# Sheet2.net
KiCad netlist of a schematic drawn in Altium Designer
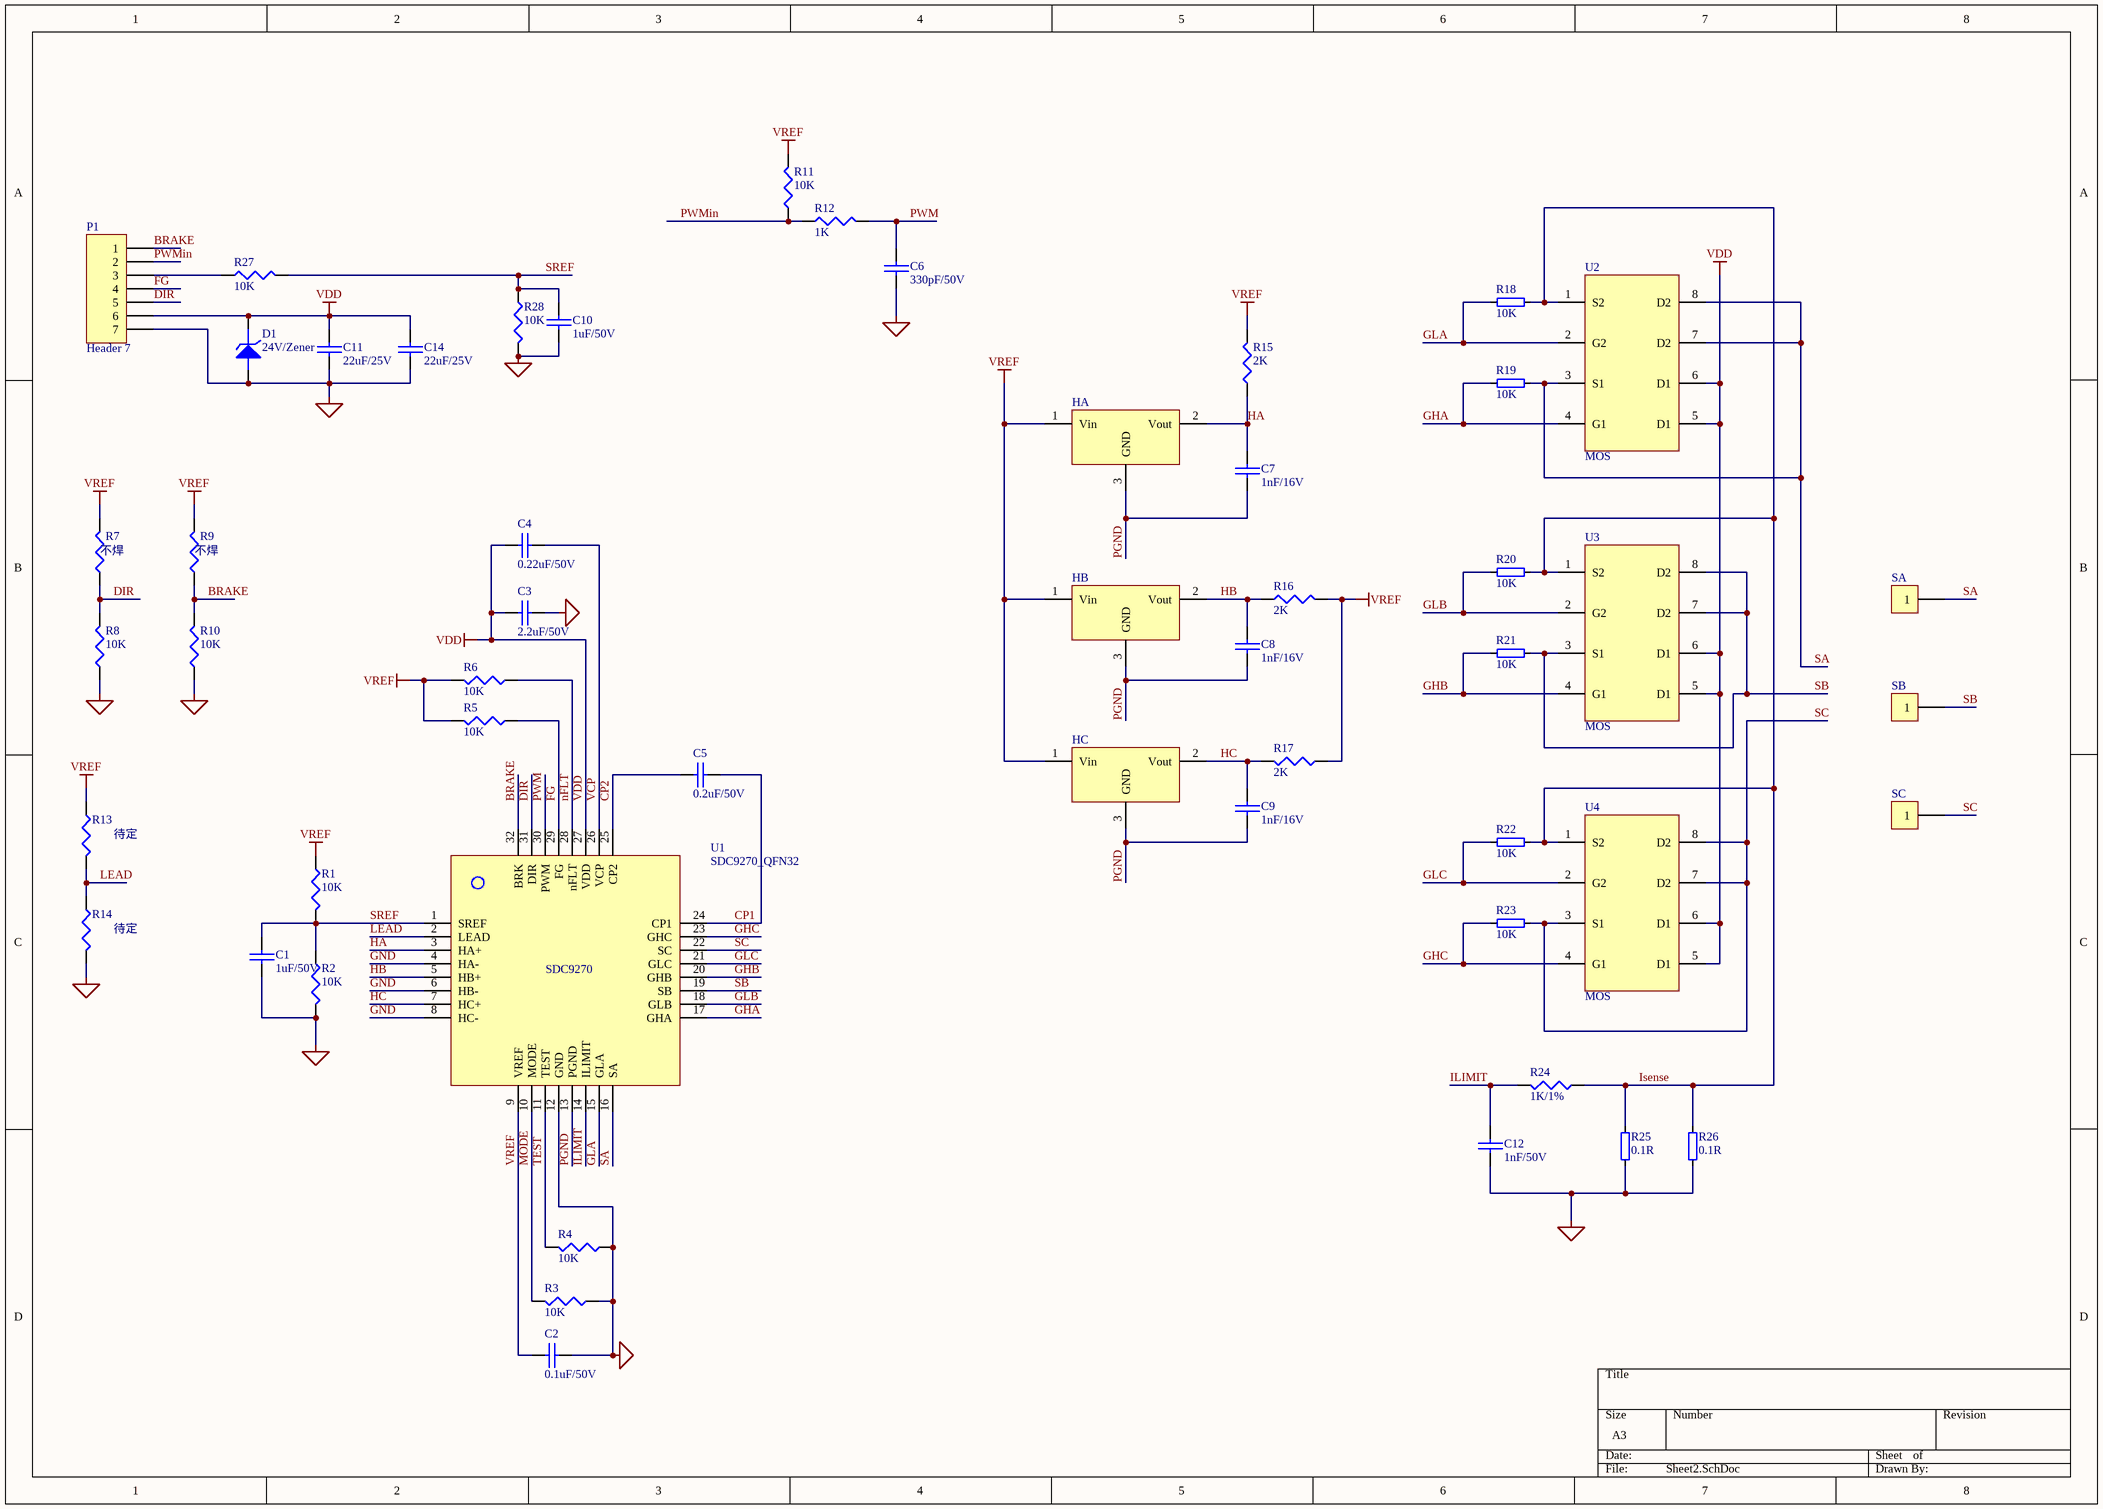
[diagram p0: Sheet2.SchDoc]

(export (version "E")
  (design (tool "Eeschema 10.0.6"))
  (components
    (comp (ref "C1")
      (value "1uF/50V")
      (footprint "6a9b1d68d1a3967c809c8143a1303d91:C0603")
      (description "C0603")
      (libsource (lib "SDC") (part "C0603"))
    )
    (comp (ref "C2")
      (value "0.1uF/50V")
      (footprint "C0603")
      (description "C0805")
      (libsource (lib "SDC") (part "C0805"))
    )
    (comp (ref "C3")
      (value "2.2uF/50V")
      (footprint "C0603")
      (description "C1206")
      (libsource (lib "SDC") (part "C1206"))
    )
    (comp (ref "C4")
      (value "0.22uF/50V")
      (footprint "C0603")
      (description "C0805")
      (libsource (lib "SDC") (part "C0805"))
    )
    (comp (ref "C5")
      (value "0.2uF/50V")
      (footprint "C0603")
      (description "C0805")
      (libsource (lib "SDC") (part "C0805"))
    )
    (comp (ref "C6")
      (value "330pF/50V")
      (footprint "C0603")
      (description "C0603")
      (libsource (lib "SDC") (part "C0603"))
    )
    (comp (ref "C7")
      (value "1nF/16V")
      (footprint "C0603")
      (description "C0603")
      (libsource (lib "SDC") (part "C0603"))
    )
    (comp (ref "C8")
      (value "1nF/16V")
      (footprint "C0603")
      (description "C0603")
      (libsource (lib "SDC") (part "C0603"))
    )
    (comp (ref "C9")
      (value "1nF/16V")
      (footprint "C0603")
      (description "C0603")
      (libsource (lib "SDC") (part "C0603"))
    )
    (comp (ref "C10")
      (value "1uF/50V")
      (footprint "C0603")
      (description "C0603")
      (libsource (lib "SDC") (part "C0603"))
    )
    (comp (ref "C11")
      (value "22uF/25V")
      (footprint "C0603")
      (description "C0603")
      (libsource (lib "SDC") (part "C0603"))
    )
    (comp (ref "C12")
      (value "1nF/50V")
      (footprint "C0603")
      (description "C0603")
      (libsource (lib "SDC") (part "C0603"))
    )
    (comp (ref "C14")
      (value "22uF/25V")
      (footprint "C0603")
      (description "C0603")
      (libsource (lib "SDC") (part "C0603"))
    )
    (comp (ref "D1")
      (value "24V/Zener")
      (footprint "SMB")
      (description "Zener Diode")
      (libsource (lib "SDC") (part "Zener_SOD-123"))
    )
    (comp (ref "HA")
      (value "HALL_SOT23-3")
      (footprint "SOT-23")
      (libsource (lib "Schlib1") (part "HALL_SOT23-3"))
    )
    (comp (ref "HB")
      (value "HALL_SOT23-3")
      (footprint "SOT-23")
      (libsource (lib "Schlib1") (part "HALL_SOT23-3"))
    )
    (comp (ref "HC")
      (value "HALL_SOT23-3")
      (footprint "SOT-23")
      (libsource (lib "Schlib1") (part "HALL_SOT23-3"))
    )
    (comp (ref "P1")
      (value "Header 7")
      (footprint "HDR1X7")
      (description "Header, 7-Pin")
      (fields (field (name "PUBLISHER") "Altium Limited"))
      (libsource (lib "Miscellaneous Connectors") (part "Header 7"))
    )
    (comp (ref "R1")
      (value "10K")
      (footprint "R0603")
      (description "R0603")
      (libsource (lib "SDC") (part "R0603"))
    )
    (comp (ref "R2")
      (value "10K")
      (footprint "R0603")
      (description "R0603")
      (libsource (lib "SDC") (part "R0603"))
    )
    (comp (ref "R3")
      (value "10K")
      (footprint "R0603")
      (description "R0603")
      (libsource (lib "SDC") (part "R0603"))
    )
    (comp (ref "R4")
      (value "10K")
      (footprint "R0603")
      (description "R0603")
      (libsource (lib "SDC") (part "R0603"))
    )
    (comp (ref "R5")
      (value "10K")
      (footprint "R0603")
      (description "R0603")
      (libsource (lib "SDC") (part "R0603"))
    )
    (comp (ref "R6")
      (value "10K")
      (footprint "R0603")
      (description "R0603")
      (libsource (lib "SDC") (part "R0603"))
    )
    (comp (ref "R7")
      (value "~")
      (footprint "R0603")
      (description "R0603")
      (libsource (lib "SDC") (part "R0603"))
    )
    (comp (ref "R8")
      (value "10K")
      (footprint "R0603")
      (description "R0603")
      (libsource (lib "SDC") (part "R0603"))
    )
    (comp (ref "R9")
      (value "~")
      (footprint "R0603")
      (description "R0603")
      (libsource (lib "SDC") (part "R0603"))
    )
    (comp (ref "R10")
      (value "10K")
      (footprint "R0603")
      (description "R0603")
      (libsource (lib "SDC") (part "R0603"))
    )
    (comp (ref "R11")
      (value "10K")
      (footprint "R0603")
      (description "R0603")
      (libsource (lib "SDC") (part "R0603"))
    )
    (comp (ref "R12")
      (value "1K")
      (footprint "R0603")
      (description "R0603")
      (libsource (lib "SDC") (part "R0603"))
    )
    (comp (ref "R13")
      (value "~")
      (footprint "R0603")
      (description "R0603")
      (libsource (lib "SDC") (part "R0603"))
    )
    (comp (ref "R14")
      (value "~")
      (footprint "R0603")
      (description "R0603")
      (libsource (lib "SDC") (part "R0603"))
    )
    (comp (ref "R15")
      (value "2K")
      (footprint "R0603")
      (description "R0603")
      (libsource (lib "SDC") (part "R0603"))
    )
    (comp (ref "R16")
      (value "2K")
      (footprint "R0603")
      (description "R0603")
      (libsource (lib "SDC") (part "R0603"))
    )
    (comp (ref "R17")
      (value "2K")
      (footprint "R0603")
      (description "R0603")
      (libsource (lib "SDC") (part "R0603"))
    )
    (comp (ref "R18") (value "10K") (footprint "R0603") (libsource (lib "SDC") (part "R1_0603")))
    (comp (ref "R19") (value "10K") (footprint "R0603") (libsource (lib "SDC") (part "R1_0603")))
    (comp (ref "R20") (value "10K") (footprint "R0603") (libsource (lib "SDC") (part "R1_0603")))
    (comp (ref "R21") (value "10K") (footprint "R0603") (libsource (lib "SDC") (part "R1_0603")))
    (comp (ref "R22") (value "10K") (footprint "R0603") (libsource (lib "SDC") (part "R1_0603")))
    (comp (ref "R23") (value "10K") (footprint "R0603") (libsource (lib "SDC") (part "R1_0603")))
    (comp (ref "R24")
      (value "1K/1%")
      (footprint "R0603")
      (description "R0603")
      (libsource (lib "SDC") (part "R0603"))
    )
    (comp (ref "R25") (value "0.1R") (footprint "R2512") (libsource (lib "SDC") (part "R2512")))
    (comp (ref "R26") (value "0.1R") (footprint "R2512") (libsource (lib "SDC") (part "R2512")))
    (comp (ref "R27")
      (value "10K")
      (footprint "R0603")
      (description "R0603")
      (libsource (lib "SDC") (part "R0603"))
    )
    (comp (ref "R28")
      (value "10K")
      (footprint "R0603")
      (description "R0603")
      (libsource (lib "SDC") (part "R0603"))
    )
    (comp (ref "SA")
      (value "~")
      (footprint "cp1")
      (description "Connector")
      (libsource (lib "Miscellaneous Devices") (part "CON1"))
    )
    (comp (ref "SB")
      (value "~")
      (footprint "cp1")
      (description "Connector")
      (libsource (lib "Miscellaneous Devices") (part "CON1"))
    )
    (comp (ref "SC")
      (value "~")
      (footprint "cp1")
      (description "Connector")
      (libsource (lib "Miscellaneous Devices") (part "CON1"))
    )
    (comp (ref "U1")
      (value "SDC9270_QFN32")
      (footprint "QFN32 (5*5)")
      (libsource (lib "9c398404867a5683d8cc0047cfd995d4") (part "SDC9270_QFN32"))
    )
    (comp (ref "U2") (value "MOS") (footprint "SOP-8") (libsource (lib "SDC") (part "MOS")))
    (comp (ref "U3") (value "MOS") (footprint "SOP-8") (libsource (lib "SDC") (part "MOS")))
    (comp (ref "U4") (value "MOS") (footprint "SOP-8") (libsource (lib "SDC") (part "MOS")))
  )
  (nets
    (net (code "1") (name "/BRAKE") (class "Default")
      (node (ref "P1") (pin "1") (pinfunction "1_1") (pintype "passive"))
      (node (ref "R10") (pin "2") (pinfunction "2_2") (pintype "passive"))
      (node (ref "R9") (pin "1") (pinfunction "1_1") (pintype "passive"))
      (node (ref "U1") (pin "32") (pinfunction "BRK_32") (pintype "passive"))
    )
    (net (code "2") (name "/CP1") (class "Default")
      (node (ref "C5") (pin "1") (pinfunction "1_1") (pintype "passive"))
      (node (ref "U1") (pin "24") (pinfunction "CP1_24") (pintype "passive"))
    )
    (net (code "3") (name "/CP2") (class "Default")
      (node (ref "C5") (pin "2") (pinfunction "2_2") (pintype "passive"))
      (node (ref "U1") (pin "25") (pinfunction "CP2_25") (pintype "passive"))
    )
    (net (code "4") (name "/DIR") (class "Default")
      (node (ref "P1") (pin "5") (pinfunction "5_5") (pintype "passive"))
      (node (ref "R7") (pin "1") (pinfunction "1_1") (pintype "passive"))
      (node (ref "R8") (pin "2") (pinfunction "2_2") (pintype "passive"))
      (node (ref "U1") (pin "31") (pinfunction "DIR_31") (pintype "passive"))
    )
    (net (code "5") (name "/FG") (class "Default")
      (node (ref "P1") (pin "4") (pinfunction "4_4") (pintype "passive"))
      (node (ref "R5") (pin "1") (pinfunction "1_1") (pintype "passive"))
      (node (ref "U1") (pin "29") (pinfunction "FG_29") (pintype "passive"))
    )
    (net (code "6") (name "/GHA") (class "Default")
      (node (ref "R19") (pin "1") (pinfunction "1_1") (pintype "passive"))
      (node (ref "U1") (pin "17") (pinfunction "GHA_17") (pintype "passive"))
      (node (ref "U2") (pin "4") (pinfunction "G1_4") (pintype "passive"))
    )
    (net (code "7") (name "/GHB") (class "Default")
      (node (ref "R21") (pin "2") (pinfunction "2_2") (pintype "passive"))
      (node (ref "U1") (pin "20") (pinfunction "GHB_20") (pintype "passive"))
      (node (ref "U3") (pin "4") (pinfunction "G1_4") (pintype "passive"))
    )
    (net (code "8") (name "/GHC") (class "Default")
      (node (ref "R23") (pin "1") (pinfunction "1_1") (pintype "passive"))
      (node (ref "U1") (pin "23") (pinfunction "GHC_23") (pintype "passive"))
      (node (ref "U4") (pin "4") (pinfunction "G1_4") (pintype "passive"))
    )
    (net (code "9") (name "/GLA") (class "Default")
      (node (ref "R18") (pin "2") (pinfunction "2_2") (pintype "passive"))
      (node (ref "U1") (pin "15") (pinfunction "GLA_15") (pintype "passive"))
      (node (ref "U2") (pin "2") (pinfunction "G2_2") (pintype "passive"))
    )
    (net (code "10") (name "/GLB") (class "Default")
      (node (ref "R20") (pin "1") (pinfunction "1_1") (pintype "passive"))
      (node (ref "U1") (pin "18") (pinfunction "GLB_18") (pintype "passive"))
      (node (ref "U3") (pin "2") (pinfunction "G2_2") (pintype "passive"))
    )
    (net (code "11") (name "/GLC") (class "Default")
      (node (ref "R22") (pin "2") (pinfunction "2_2") (pintype "passive"))
      (node (ref "U1") (pin "21") (pinfunction "GLC_21") (pintype "passive"))
      (node (ref "U4") (pin "2") (pinfunction "G2_2") (pintype "passive"))
    )
    (net (code "12") (name "/GND") (class "Default")
      (node (ref "U1") (pin "4") (pinfunction "HA-_4") (pintype "passive"))
      (node (ref "U1") (pin "6") (pinfunction "HB-_6") (pintype "passive"))
      (node (ref "U1") (pin "8") (pinfunction "HC-_8") (pintype "passive"))
    )
    (net (code "13") (name "/HA") (class "Default")
      (node (ref "C7") (pin "2") (pinfunction "2_2") (pintype "passive"))
      (node (ref "HA") (pin "2") (pinfunction "Vout_2") (pintype "passive"))
      (node (ref "R15") (pin "1") (pinfunction "1_1") (pintype "passive"))
      (node (ref "U1") (pin "3") (pinfunction "HA+_3") (pintype "passive"))
    )
    (net (code "14") (name "/HB") (class "Default")
      (node (ref "C8") (pin "2") (pinfunction "2_2") (pintype "passive"))
      (node (ref "HB") (pin "2") (pinfunction "Vout_2") (pintype "passive"))
      (node (ref "R16") (pin "1") (pinfunction "1_1") (pintype "passive"))
      (node (ref "U1") (pin "5") (pinfunction "HB+_5") (pintype "passive"))
    )
    (net (code "15") (name "/HC") (class "Default")
      (node (ref "C9") (pin "2") (pinfunction "2_2") (pintype "passive"))
      (node (ref "HC") (pin "2") (pinfunction "Vout_2") (pintype "passive"))
      (node (ref "R17") (pin "2") (pinfunction "2_2") (pintype "passive"))
      (node (ref "U1") (pin "7") (pinfunction "HC+_7") (pintype "passive"))
    )
    (net (code "16") (name "/ILIMIT") (class "Default")
      (node (ref "C12") (pin "2") (pinfunction "2_2") (pintype "passive"))
      (node (ref "R24") (pin "2") (pinfunction "2_2") (pintype "passive"))
      (node (ref "U1") (pin "14") (pinfunction "ILIMIT_14") (pintype "passive"))
    )
    (net (code "17") (name "/Isense") (class "Default")
      (node (ref "R18") (pin "1") (pinfunction "1_1") (pintype "passive"))
      (node (ref "R20") (pin "2") (pinfunction "2_2") (pintype "passive"))
      (node (ref "R22") (pin "1") (pinfunction "1_1") (pintype "passive"))
      (node (ref "R24") (pin "1") (pinfunction "1_1") (pintype "passive"))
      (node (ref "R25") (pin "2") (pinfunction "2_2") (pintype "passive"))
      (node (ref "R26") (pin "2") (pinfunction "2_2") (pintype "passive"))
      (node (ref "U2") (pin "1") (pinfunction "S2_1") (pintype "passive"))
      (node (ref "U3") (pin "1") (pinfunction "S2_1") (pintype "passive"))
      (node (ref "U4") (pin "1") (pinfunction "S2_1") (pintype "passive"))
    )
    (net (code "18") (name "/LEAD") (class "Default")
      (node (ref "R13") (pin "2") (pinfunction "2_2") (pintype "passive"))
      (node (ref "R14") (pin "1") (pinfunction "1_1") (pintype "passive"))
      (node (ref "U1") (pin "2") (pinfunction "LEAD_2") (pintype "passive"))
    )
    (net (code "19") (name "/MODE") (class "Default")
      (node (ref "R3") (pin "2") (pinfunction "2_2") (pintype "passive"))
      (node (ref "U1") (pin "10") (pinfunction "MODE_10") (pintype "passive"))
    )
    (net (code "20") (name "/PGND") (class "Default")
      (node (ref "C7") (pin "1") (pinfunction "1_1") (pintype "passive"))
      (node (ref "C8") (pin "1") (pinfunction "1_1") (pintype "passive"))
      (node (ref "C9") (pin "1") (pinfunction "1_1") (pintype "passive"))
      (node (ref "HA") (pin "3") (pinfunction "GND_3") (pintype "passive"))
      (node (ref "HB") (pin "3") (pinfunction "GND_3") (pintype "passive"))
      (node (ref "HC") (pin "3") (pinfunction "GND_3") (pintype "passive"))
      (node (ref "U1") (pin "13") (pinfunction "PGND_13") (pintype "passive"))
    )
    (net (code "21") (name "/PWM") (class "Default")
      (node (ref "C6") (pin "2") (pinfunction "2_2") (pintype "passive"))
      (node (ref "R12") (pin "2") (pinfunction "2_2") (pintype "passive"))
      (node (ref "U1") (pin "30") (pinfunction "PWM_30") (pintype "passive"))
    )
    (net (code "22") (name "/PWMin") (class "Default")
      (node (ref "P1") (pin "2") (pinfunction "2_2") (pintype "passive"))
      (node (ref "R11") (pin "1") (pinfunction "1_1") (pintype "passive"))
      (node (ref "R12") (pin "1") (pinfunction "1_1") (pintype "passive"))
    )
    (net (code "23") (name "/SA") (class "Default")
      (node (ref "R19") (pin "2") (pinfunction "2_2") (pintype "passive"))
      (node (ref "SA") (pin "1") (pinfunction "1_1") (pintype "passive"))
      (node (ref "U1") (pin "16") (pinfunction "SA_16") (pintype "passive"))
      (node (ref "U2") (pin "3") (pinfunction "S1_3") (pintype "passive"))
      (node (ref "U2") (pin "7") (pinfunction "D2_7") (pintype "passive"))
      (node (ref "U2") (pin "8") (pinfunction "D2_8") (pintype "passive"))
    )
    (net (code "24") (name "/SB") (class "Default")
      (node (ref "R21") (pin "1") (pinfunction "1_1") (pintype "passive"))
      (node (ref "SB") (pin "1") (pinfunction "1_1") (pintype "passive"))
      (node (ref "U1") (pin "19") (pinfunction "SB_19") (pintype "passive"))
      (node (ref "U3") (pin "3") (pinfunction "S1_3") (pintype "passive"))
      (node (ref "U3") (pin "7") (pinfunction "D2_7") (pintype "passive"))
      (node (ref "U3") (pin "8") (pinfunction "D2_8") (pintype "passive"))
    )
    (net (code "25") (name "/SC") (class "Default")
      (node (ref "R23") (pin "2") (pinfunction "2_2") (pintype "passive"))
      (node (ref "SC") (pin "1") (pinfunction "1_1") (pintype "passive"))
      (node (ref "U1") (pin "22") (pinfunction "SC_22") (pintype "passive"))
      (node (ref "U4") (pin "3") (pinfunction "S1_3") (pintype "passive"))
      (node (ref "U4") (pin "7") (pinfunction "D2_7") (pintype "passive"))
      (node (ref "U4") (pin "8") (pinfunction "D2_8") (pintype "passive"))
    )
    (net (code "26") (name "/SREF") (class "Default")
      (node (ref "C1") (pin "1") (pinfunction "1_1") (pintype "passive"))
      (node (ref "C10") (pin "1") (pinfunction "1_1") (pintype "passive"))
      (node (ref "R1") (pin "2") (pinfunction "2_2") (pintype "passive"))
      (node (ref "R2") (pin "1") (pinfunction "1_1") (pintype "passive"))
      (node (ref "R27") (pin "2") (pinfunction "2_2") (pintype "passive"))
      (node (ref "R28") (pin "1") (pinfunction "1_1") (pintype "passive"))
      (node (ref "U1") (pin "1") (pinfunction "SREF_1") (pintype "passive"))
    )
    (net (code "27") (name "/TEST") (class "Default")
      (node (ref "R4") (pin "2") (pinfunction "2_2") (pintype "passive"))
      (node (ref "U1") (pin "11") (pinfunction "TEST_11") (pintype "passive"))
    )
    (net (code "28") (name "/VCP") (class "Default")
      (node (ref "C4") (pin "2") (pinfunction "2_2") (pintype "passive"))
      (node (ref "U1") (pin "26") (pinfunction "VCP_26") (pintype "passive"))
    )
    (net (code "29") (name "/nFLT") (class "Default")
      (node (ref "R6") (pin "1") (pinfunction "1_1") (pintype "passive"))
      (node (ref "U1") (pin "28") (pinfunction "nFLT_28") (pintype "passive"))
    )
    (net (code "30") (name "Net-(P1-Pad3)") (class "Default")
      (node (ref "P1") (pin "3") (pinfunction "3_3") (pintype "passive"))
      (node (ref "R27") (pin "1") (pinfunction "1_1") (pintype "passive"))
    )
    (net (code "31") (name "SGND") (class "Default")
      (node (ref "C1") (pin "2") (pinfunction "2_2") (pintype "passive"))
      (node (ref "C10") (pin "2") (pinfunction "2_2") (pintype "passive"))
      (node (ref "C11") (pin "1") (pinfunction "1_1") (pintype "passive"))
      (node (ref "C12") (pin "1") (pinfunction "1_1") (pintype "passive"))
      (node (ref "C14") (pin "1") (pinfunction "1_1") (pintype "passive"))
      (node (ref "C2") (pin "1") (pinfunction "1_1") (pintype "passive"))
      (node (ref "C3") (pin "2") (pinfunction "2_2") (pintype "passive"))
      (node (ref "C6") (pin "1") (pinfunction "1_1") (pintype "passive"))
      (node (ref "D1") (pin "1") (pinfunction "A_1") (pintype "passive"))
      (node (ref "P1") (pin "7") (pinfunction "7_7") (pintype "passive"))
      (node (ref "R10") (pin "1") (pinfunction "1_1") (pintype "passive"))
      (node (ref "R14") (pin "2") (pinfunction "2_2") (pintype "passive"))
      (node (ref "R2") (pin "2") (pinfunction "2_2") (pintype "passive"))
      (node (ref "R25") (pin "1") (pinfunction "1_1") (pintype "passive"))
      (node (ref "R26") (pin "1") (pinfunction "1_1") (pintype "passive"))
      (node (ref "R28") (pin "2") (pinfunction "2_2") (pintype "passive"))
      (node (ref "R3") (pin "1") (pinfunction "1_1") (pintype "passive"))
      (node (ref "R4") (pin "1") (pinfunction "1_1") (pintype "passive"))
      (node (ref "R8") (pin "1") (pinfunction "1_1") (pintype "passive"))
      (node (ref "U1") (pin "12") (pinfunction "GND_12") (pintype "passive"))
    )
    (net (code "32") (name "VDD") (class "Default")
      (node (ref "C11") (pin "2") (pinfunction "2_2") (pintype "passive"))
      (node (ref "C14") (pin "2") (pinfunction "2_2") (pintype "passive"))
      (node (ref "C3") (pin "1") (pinfunction "1_1") (pintype "passive"))
      (node (ref "C4") (pin "1") (pinfunction "1_1") (pintype "passive"))
      (node (ref "D1") (pin "2") (pinfunction "K_2") (pintype "passive"))
      (node (ref "P1") (pin "6") (pinfunction "6_6") (pintype "passive"))
      (node (ref "U1") (pin "27") (pinfunction "VDD_27") (pintype "passive"))
      (node (ref "U2") (pin "5") (pinfunction "D1_5") (pintype "passive"))
      (node (ref "U2") (pin "6") (pinfunction "D1_6") (pintype "passive"))
      (node (ref "U3") (pin "5") (pinfunction "D1_5") (pintype "passive"))
      (node (ref "U3") (pin "6") (pinfunction "D1_6") (pintype "passive"))
      (node (ref "U4") (pin "5") (pinfunction "D1_5") (pintype "passive"))
      (node (ref "U4") (pin "6") (pinfunction "D1_6") (pintype "passive"))
    )
    (net (code "33") (name "VREF") (class "Default")
      (node (ref "C2") (pin "2") (pinfunction "2_2") (pintype "passive"))
      (node (ref "HA") (pin "1") (pinfunction "Vin_1") (pintype "passive"))
      (node (ref "HB") (pin "1") (pinfunction "Vin_1") (pintype "passive"))
      (node (ref "HC") (pin "1") (pinfunction "Vin_1") (pintype "passive"))
      (node (ref "R1") (pin "1") (pinfunction "1_1") (pintype "passive"))
      (node (ref "R11") (pin "2") (pinfunction "2_2") (pintype "passive"))
      (node (ref "R13") (pin "1") (pinfunction "1_1") (pintype "passive"))
      (node (ref "R15") (pin "2") (pinfunction "2_2") (pintype "passive"))
      (node (ref "R16") (pin "2") (pinfunction "2_2") (pintype "passive"))
      (node (ref "R17") (pin "1") (pinfunction "1_1") (pintype "passive"))
      (node (ref "R5") (pin "2") (pinfunction "2_2") (pintype "passive"))
      (node (ref "R6") (pin "2") (pinfunction "2_2") (pintype "passive"))
      (node (ref "R7") (pin "2") (pinfunction "2_2") (pintype "passive"))
      (node (ref "R9") (pin "2") (pinfunction "2_2") (pintype "passive"))
      (node (ref "U1") (pin "9") (pinfunction "VREF_9") (pintype "passive"))
    )
  )
)
